# FOUR-INPORT.net
KiCad netlist of a schematic drawn in Altium Designer
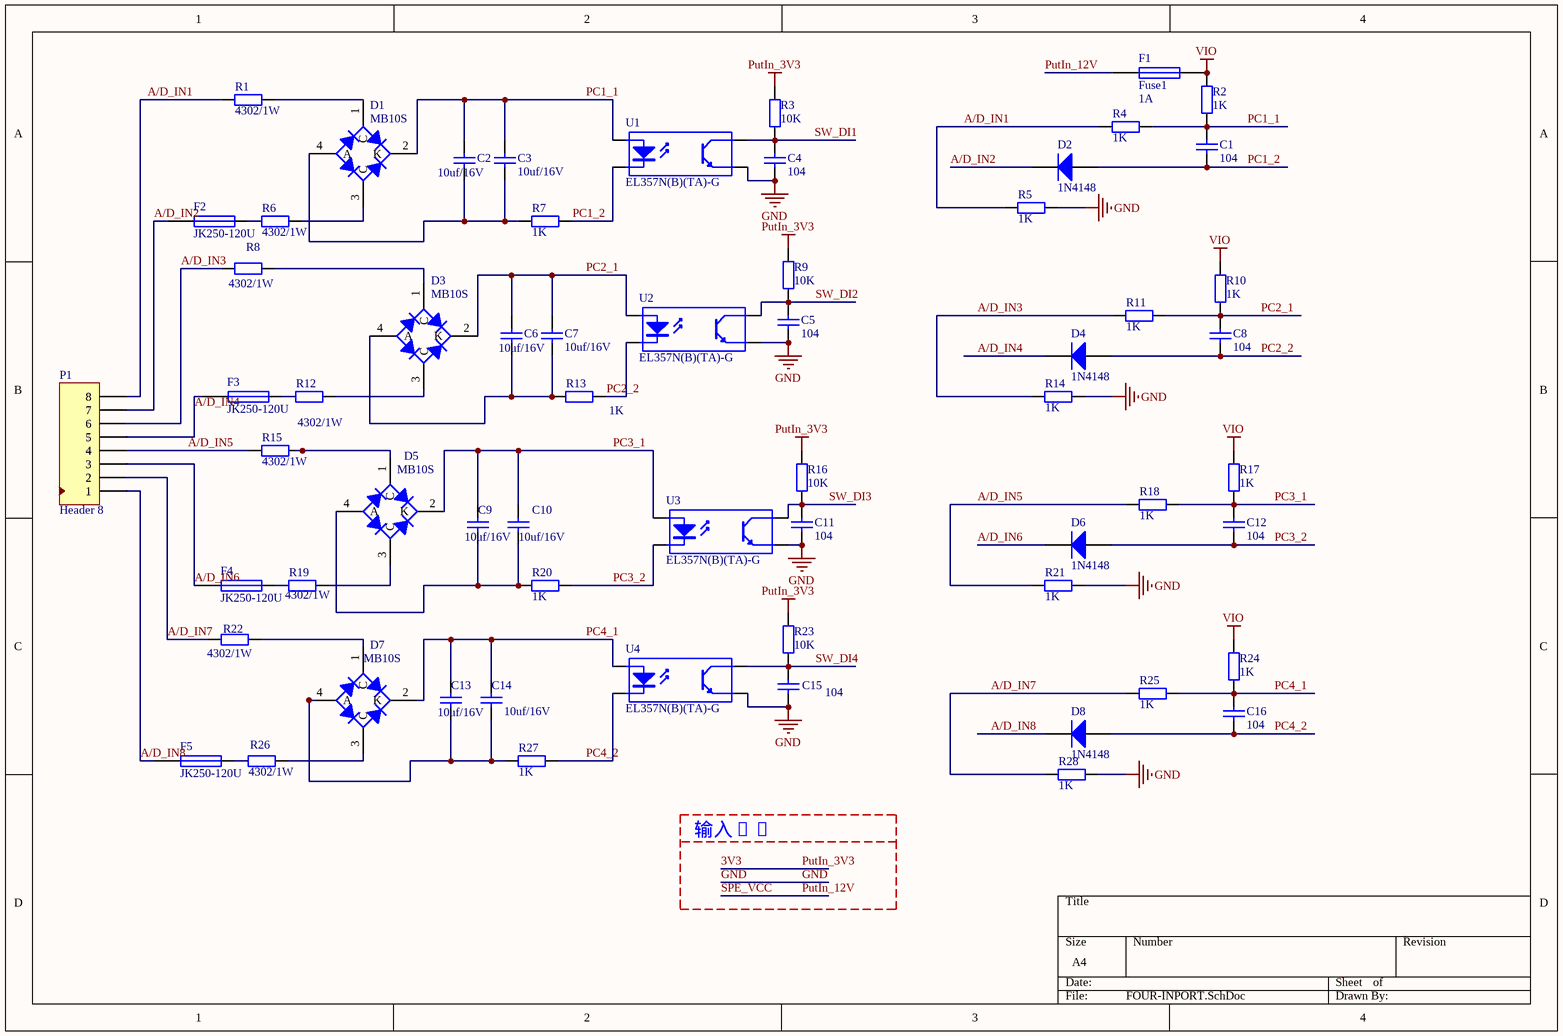
[diagram p0: FOUR-INPORT.SchDoc]

(export (version "E")
  (design (tool "Eeschema 10.0.6"))
  (components
    (comp (ref "C1")
      (value "104")
      (footprint "LC-1206_C")
      (description "Capacitor")
      (fields (field (name "PUBLISHER") "Altium Limited"))
      (libsource (lib "Miscellaneous Devices") (part "Cap"))
    )
    (comp (ref "C2")
      (value "10uf/16V")
      (footprint "LC-0805_C")
      (description "Capacitor")
      (fields (field (name "PUBLISHER") "Altium Limited"))
      (libsource (lib "Miscellaneous Devices") (part "Cap"))
    )
    (comp (ref "C3")
      (value "10uf/16V")
      (footprint "LC-0805_C")
      (description "Capacitor")
      (fields (field (name "PUBLISHER") "Altium Limited"))
      (libsource (lib "Miscellaneous Devices") (part "Cap"))
    )
    (comp (ref "C4")
      (value "104")
      (footprint "LC-0603_C")
      (description "Capacitor")
      (fields (field (name "PUBLISHER") "Altium Limited"))
      (libsource (lib "Miscellaneous Devices") (part "Cap"))
    )
    (comp (ref "C5")
      (value "104")
      (footprint "LC-0603_C")
      (description "Capacitor")
      (fields (field (name "PUBLISHER") "Altium Limited"))
      (libsource (lib "Miscellaneous Devices") (part "Cap"))
    )
    (comp (ref "C6")
      (value "10uf/16V")
      (footprint "LC-0805_C")
      (description "Capacitor")
      (fields (field (name "PUBLISHER") "Altium Limited"))
      (libsource (lib "Miscellaneous Devices") (part "Cap"))
    )
    (comp (ref "C7")
      (value "10uf/16V")
      (footprint "LC-0805_C")
      (description "Capacitor")
      (fields (field (name "PUBLISHER") "Altium Limited"))
      (libsource (lib "Miscellaneous Devices") (part "Cap"))
    )
    (comp (ref "C8")
      (value "104")
      (footprint "LC-1206_C")
      (description "Capacitor")
      (fields (field (name "PUBLISHER") "Altium Limited"))
      (libsource (lib "Miscellaneous Devices") (part "Cap"))
    )
    (comp (ref "C9")
      (value "10uf/16V")
      (footprint "LC-0805_C")
      (description "Capacitor")
      (fields (field (name "PUBLISHER") "Altium Limited"))
      (libsource (lib "Miscellaneous Devices") (part "Cap"))
    )
    (comp (ref "C10")
      (value "10uf/16V")
      (footprint "LC-0805_C")
      (description "Capacitor")
      (fields (field (name "PUBLISHER") "Altium Limited"))
      (libsource (lib "Miscellaneous Devices") (part "Cap"))
    )
    (comp (ref "C11")
      (value "104")
      (footprint "LC-0603_C")
      (description "Capacitor")
      (fields (field (name "PUBLISHER") "Altium Limited"))
      (libsource (lib "Miscellaneous Devices") (part "Cap"))
    )
    (comp (ref "C12")
      (value "104")
      (footprint "LC-1206_C")
      (description "Capacitor")
      (fields (field (name "PUBLISHER") "Altium Limited"))
      (libsource (lib "Miscellaneous Devices") (part "Cap"))
    )
    (comp (ref "C13")
      (value "10uf/16V")
      (footprint "LC-0805_C")
      (description "Capacitor")
      (fields (field (name "PUBLISHER") "Altium Limited"))
      (libsource (lib "Miscellaneous Devices") (part "Cap"))
    )
    (comp (ref "C14")
      (value "10uf/16V")
      (footprint "LC-0805_C")
      (description "Capacitor")
      (fields (field (name "PUBLISHER") "Altium Limited"))
      (libsource (lib "Miscellaneous Devices") (part "Cap"))
    )
    (comp (ref "C15")
      (value "104")
      (footprint "LC-0603_C")
      (description "Capacitor")
      (fields (field (name "PUBLISHER") "Altium Limited"))
      (libsource (lib "Miscellaneous Devices") (part "Cap"))
    )
    (comp (ref "C16")
      (value "104")
      (footprint "LC-1206_C")
      (description "Capacitor")
      (fields (field (name "PUBLISHER") "Altium Limited"))
      (libsource (lib "Miscellaneous Devices") (part "Cap"))
    )
    (comp (ref "D1")
      (value "MB10S")
      (footprint "LC-MBS")
      (description "整流桥")
      (libsource (lib "Miscellaneous Devices LC") (part "MBS MB10S"))
    )
    (comp (ref "D2")
      (value "1N4148")
      (footprint "LC-LL-34")
      (description "Default Diode")
      (fields (field (name "PUBLISHER") "Altium Limited"))
      (libsource (lib "Miscellaneous Devices") (part "Diode"))
    )
    (comp (ref "D3")
      (value "MB10S")
      (footprint "LC-MBS")
      (description "整流桥")
      (libsource (lib "Miscellaneous Devices LC") (part "MBS MB10S"))
    )
    (comp (ref "D4")
      (value "1N4148")
      (footprint "LC-LL-34")
      (description "Default Diode")
      (fields (field (name "PUBLISHER") "Altium Limited"))
      (libsource (lib "Miscellaneous Devices") (part "Diode"))
    )
    (comp (ref "D5")
      (value "MB10S")
      (footprint "LC-MBS")
      (description "整流桥")
      (libsource (lib "Miscellaneous Devices LC") (part "MBS MB10S"))
    )
    (comp (ref "D6")
      (value "1N4148")
      (footprint "LC-LL-34")
      (description "Default Diode")
      (fields (field (name "PUBLISHER") "Altium Limited"))
      (libsource (lib "Miscellaneous Devices") (part "Diode"))
    )
    (comp (ref "D7")
      (value "MB10S")
      (footprint "LC-MBS")
      (description "整流桥")
      (libsource (lib "Miscellaneous Devices LC") (part "MBS MB10S"))
    )
    (comp (ref "D8")
      (value "1N4148")
      (footprint "LC-LL-34")
      (description "Default Diode")
      (fields (field (name "PUBLISHER") "Altium Limited"))
      (libsource (lib "Miscellaneous Devices") (part "Diode"))
    )
    (comp (ref "F1")
      (value "Fuse1")
      (footprint "LC-1206_R")
      (description "保险丝")
      (fields (field (name "ALTIUM_VALUE") "1A"))
      (libsource (lib "fszhang") (part "Fuse1"))
    )
    (comp (ref "F2")
      (value "JK250-120U")
      (footprint "ntc250v")
      (description "保险丝")
      (libsource (lib "SCH_Footp1_Lian") (part "Fuse1"))
    )
    (comp (ref "F3")
      (value "JK250-120U")
      (footprint "ntc250v")
      (description "保险丝")
      (libsource (lib "SCH_Footp1_Lian") (part "Fuse1"))
    )
    (comp (ref "F4")
      (value "JK250-120U")
      (footprint "ntc250v")
      (description "保险丝")
      (libsource (lib "SCH_Footp1_Lian") (part "Fuse1"))
    )
    (comp (ref "F5")
      (value "JK250-120U")
      (footprint "ntc250v")
      (description "保险丝")
      (libsource (lib "SCH_Footp1_Lian") (part "Fuse1"))
    )
    (comp (ref "P1")
      (value "Header 8")
      (footprint "5.08-8p")
      (description "接插件")
      (fields (field (name "PUBLISHER") "Altium Limited"))
      (libsource (lib "HDR_fszhang") (part "Header 8"))
    )
    (comp (ref "R1")
      (value "4302/1W")
      (footprint "LC-2512_R")
      (description "Resistor")
      (fields (field (name "PUBLISHER") "Altium Limited"))
      (libsource (lib "Miscellaneous Devices") (part "Res2"))
    )
    (comp (ref "R2")
      (value "1K")
      (footprint "LC-1206_R")
      (description "贴片电阻")
      (fields (field (name "Comment") "Res1") (field (name "PUBLISHER") "Altium Limited"))
      (libsource (lib "") (part "Res1_1"))
    )
    (comp (ref "R3")
      (value "10K")
      (footprint "LC-0603_R")
      (description "Resistor")
      (fields (field (name "PUBLISHER") "Altium Limited"))
      (libsource (lib "") (part "Res2_1"))
    )
    (comp (ref "R4")
      (value "1K")
      (footprint "LC-1206_R")
      (description "贴片电阻")
      (fields (field (name "Comment") "Res1") (field (name "PUBLISHER") "Altium Limited"))
      (libsource (lib "fszhang") (part "Res1"))
    )
    (comp (ref "R5")
      (value "1K")
      (footprint "LC-1206_R")
      (description "贴片电阻")
      (fields (field (name "Comment") "Res1") (field (name "PUBLISHER") "Altium Limited"))
      (libsource (lib "fszhang") (part "Res1"))
    )
    (comp (ref "R6")
      (value "4302/1W")
      (footprint "LC-2512_R")
      (description "Resistor")
      (fields (field (name "PUBLISHER") "Altium Limited"))
      (libsource (lib "Miscellaneous Devices") (part "Res2"))
    )
    (comp (ref "R7")
      (value "1K")
      (footprint "LC-0603_R")
      (description "Resistor")
      (fields (field (name "PUBLISHER") "Altium Limited"))
      (libsource (lib "") (part "Res2_2"))
    )
    (comp (ref "R8")
      (value "4302/1W")
      (footprint "LC-2512_R")
      (description "Resistor")
      (fields (field (name "PUBLISHER") "Altium Limited"))
      (libsource (lib "Miscellaneous Devices") (part "Res2"))
    )
    (comp (ref "R9")
      (value "10K")
      (footprint "LC-0603_R")
      (description "Resistor")
      (fields (field (name "PUBLISHER") "Altium Limited"))
      (libsource (lib "") (part "Res2_1"))
    )
    (comp (ref "R10")
      (value "1K")
      (footprint "LC-1206_R")
      (description "贴片电阻")
      (fields (field (name "Comment") "Res1") (field (name "PUBLISHER") "Altium Limited"))
      (libsource (lib "") (part "Res1_2"))
    )
    (comp (ref "R11")
      (value "1K")
      (footprint "LC-1206_R")
      (description "贴片电阻")
      (fields (field (name "Comment") "Res1") (field (name "PUBLISHER") "Altium Limited"))
      (libsource (lib "fszhang") (part "Res1"))
    )
    (comp (ref "R12")
      (value "4302/1W")
      (footprint "LC-2512_R")
      (description "Resistor")
      (fields (field (name "PUBLISHER") "Altium Limited"))
      (libsource (lib "Miscellaneous Devices") (part "Res2"))
    )
    (comp (ref "R13")
      (value "1K")
      (footprint "LC-0603_R")
      (description "Resistor")
      (fields (field (name "PUBLISHER") "Altium Limited"))
      (libsource (lib "") (part "Res2_2"))
    )
    (comp (ref "R14")
      (value "1K")
      (footprint "LC-1206_R")
      (description "贴片电阻")
      (fields (field (name "Comment") "Res1") (field (name "PUBLISHER") "Altium Limited"))
      (libsource (lib "fszhang") (part "Res1"))
    )
    (comp (ref "R15")
      (value "4302/1W")
      (footprint "LC-2512_R")
      (description "Resistor")
      (fields (field (name "PUBLISHER") "Altium Limited"))
      (libsource (lib "Miscellaneous Devices") (part "Res2"))
    )
    (comp (ref "R16")
      (value "10K")
      (footprint "LC-0603_R")
      (description "Resistor")
      (fields (field (name "PUBLISHER") "Altium Limited"))
      (libsource (lib "") (part "Res2_1"))
    )
    (comp (ref "R17")
      (value "1K")
      (footprint "LC-1206_R")
      (description "贴片电阻")
      (fields (field (name "Comment") "Res1") (field (name "PUBLISHER") "Altium Limited"))
      (libsource (lib "") (part "Res1_2"))
    )
    (comp (ref "R18")
      (value "1K")
      (footprint "LC-1206_R")
      (description "贴片电阻")
      (fields (field (name "Comment") "Res1") (field (name "PUBLISHER") "Altium Limited"))
      (libsource (lib "fszhang") (part "Res1"))
    )
    (comp (ref "R19")
      (value "4302/1W")
      (footprint "LC-2512_R")
      (description "Resistor")
      (fields (field (name "PUBLISHER") "Altium Limited"))
      (libsource (lib "Miscellaneous Devices") (part "Res2"))
    )
    (comp (ref "R20")
      (value "1K")
      (footprint "LC-0603_R")
      (description "Resistor")
      (fields (field (name "PUBLISHER") "Altium Limited"))
      (libsource (lib "") (part "Res2_2"))
    )
    (comp (ref "R21")
      (value "1K")
      (footprint "LC-1206_R")
      (description "贴片电阻")
      (fields (field (name "Comment") "Res1") (field (name "PUBLISHER") "Altium Limited"))
      (libsource (lib "fszhang") (part "Res1"))
    )
    (comp (ref "R22")
      (value "4302/1W")
      (footprint "LC-2512_R")
      (description "Resistor")
      (fields (field (name "PUBLISHER") "Altium Limited"))
      (libsource (lib "Miscellaneous Devices") (part "Res2"))
    )
    (comp (ref "R23")
      (value "10K")
      (footprint "LC-0603_R")
      (description "Resistor")
      (fields (field (name "PUBLISHER") "Altium Limited"))
      (libsource (lib "") (part "Res2_1"))
    )
    (comp (ref "R24")
      (value "1K")
      (footprint "LC-1206_R")
      (description "贴片电阻")
      (fields (field (name "Comment") "Res1") (field (name "PUBLISHER") "Altium Limited"))
      (libsource (lib "") (part "Res1_2"))
    )
    (comp (ref "R25")
      (value "1K")
      (footprint "LC-1206_R")
      (description "贴片电阻")
      (fields (field (name "Comment") "Res1") (field (name "PUBLISHER") "Altium Limited"))
      (libsource (lib "fszhang") (part "Res1"))
    )
    (comp (ref "R26")
      (value "4302/1W")
      (footprint "LC-2512_R")
      (description "Resistor")
      (fields (field (name "PUBLISHER") "Altium Limited"))
      (libsource (lib "Miscellaneous Devices") (part "Res2"))
    )
    (comp (ref "R27")
      (value "1K")
      (footprint "LC-0603_R")
      (description "Resistor")
      (fields (field (name "PUBLISHER") "Altium Limited"))
      (libsource (lib "") (part "Res2_2"))
    )
    (comp (ref "R28")
      (value "1K")
      (footprint "LC-1206_R")
      (description "贴片电阻")
      (fields (field (name "Comment") "Res1") (field (name "PUBLISHER") "Altium Limited"))
      (libsource (lib "fszhang") (part "Res1"))
    )
    (comp (ref "U1")
      (value "EL357N(B)(TA)-G")
      (footprint "LC-SOP-4_P2.54")
      (description "贴片光耦")
      (libsource (lib "Miscellaneous Devices LC") (part "EL357N(B)(TA)-G"))
    )
    (comp (ref "U2")
      (value "EL357N(B)(TA)-G")
      (footprint "LC-SOP-4_P2.54")
      (description "贴片光耦")
      (libsource (lib "Miscellaneous Devices LC") (part "EL357N(B)(TA)-G"))
    )
    (comp (ref "U3")
      (value "EL357N(B)(TA)-G")
      (footprint "LC-SOP-4_P2.54")
      (description "贴片光耦")
      (libsource (lib "Miscellaneous Devices LC") (part "EL357N(B)(TA)-G"))
    )
    (comp (ref "U4")
      (value "EL357N(B)(TA)-G")
      (footprint "LC-SOP-4_P2.54")
      (description "贴片光耦")
      (libsource (lib "Miscellaneous Devices LC") (part "EL357N(B)(TA)-G"))
    )
  )
  (nets
    (net (code "1") (name "/A{slash}D_IN1") (class "Default")
      (node (ref "P1") (pin "8") (pinfunction "8_8") (pintype "passive"))
      (node (ref "R1") (pin "1") (pinfunction "1_1") (pintype "passive"))
      (node (ref "R4") (pin "2") (pinfunction "2_2") (pintype "passive"))
      (node (ref "R5") (pin "2") (pinfunction "2_2") (pintype "passive"))
    )
    (net (code "2") (name "/A{slash}D_IN2") (class "Default")
      (node (ref "D2") (pin "2") (pinfunction "K_2") (pintype "passive"))
      (node (ref "F2") (pin "1") (pinfunction "1_1") (pintype "passive"))
      (node (ref "P1") (pin "7") (pinfunction "7_7") (pintype "passive"))
    )
    (net (code "3") (name "/A{slash}D_IN3") (class "Default")
      (node (ref "P1") (pin "6") (pinfunction "6_6") (pintype "passive"))
      (node (ref "R11") (pin "2") (pinfunction "2_2") (pintype "passive"))
      (node (ref "R14") (pin "2") (pinfunction "2_2") (pintype "passive"))
      (node (ref "R8") (pin "1") (pinfunction "1_1") (pintype "passive"))
    )
    (net (code "4") (name "/A{slash}D_IN4") (class "Default")
      (node (ref "D4") (pin "2") (pinfunction "K_2") (pintype "passive"))
      (node (ref "F3") (pin "1") (pinfunction "1_1") (pintype "passive"))
      (node (ref "P1") (pin "5") (pinfunction "5_5") (pintype "passive"))
    )
    (net (code "5") (name "/A{slash}D_IN5") (class "Default")
      (node (ref "P1") (pin "4") (pinfunction "4_4") (pintype "passive"))
      (node (ref "R15") (pin "1") (pinfunction "1_1") (pintype "passive"))
      (node (ref "R18") (pin "2") (pinfunction "2_2") (pintype "passive"))
      (node (ref "R21") (pin "2") (pinfunction "2_2") (pintype "passive"))
    )
    (net (code "6") (name "/A{slash}D_IN6") (class "Default")
      (node (ref "D6") (pin "2") (pinfunction "K_2") (pintype "passive"))
      (node (ref "F4") (pin "1") (pinfunction "1_1") (pintype "passive"))
      (node (ref "P1") (pin "3") (pinfunction "3_3") (pintype "passive"))
    )
    (net (code "7") (name "/A{slash}D_IN7") (class "Default")
      (node (ref "P1") (pin "2") (pinfunction "2_2") (pintype "passive"))
      (node (ref "R22") (pin "1") (pinfunction "1_1") (pintype "passive"))
      (node (ref "R25") (pin "2") (pinfunction "2_2") (pintype "passive"))
      (node (ref "R28") (pin "2") (pinfunction "2_2") (pintype "passive"))
    )
    (net (code "8") (name "/A{slash}D_IN8") (class "Default")
      (node (ref "D8") (pin "2") (pinfunction "K_2") (pintype "passive"))
      (node (ref "F5") (pin "1") (pinfunction "1_1") (pintype "passive"))
      (node (ref "P1") (pin "1") (pinfunction "1_1") (pintype "passive"))
    )
    (net (code "9") (name "/PC1_1") (class "Default")
      (node (ref "C1") (pin "1") (pinfunction "1_1") (pintype "passive"))
      (node (ref "C2") (pin "2") (pinfunction "2_2") (pintype "passive"))
      (node (ref "C3") (pin "2") (pinfunction "2_2") (pintype "passive"))
      (node (ref "D1") (pin "2") (pinfunction "K_2") (pintype "passive"))
      (node (ref "R2") (pin "1") (pinfunction "1_1") (pintype "passive"))
      (node (ref "R4") (pin "1") (pinfunction "1_1") (pintype "passive"))
      (node (ref "U1") (pin "1") (pinfunction "A_1") (pintype "passive"))
    )
    (net (code "10") (name "/PC1_2") (class "Default")
      (node (ref "C1") (pin "2") (pinfunction "2_2") (pintype "passive"))
      (node (ref "D2") (pin "1") (pinfunction "A_1") (pintype "passive"))
      (node (ref "R7") (pin "1") (pinfunction "1_1") (pintype "passive"))
      (node (ref "U1") (pin "2") (pinfunction "K_2") (pintype "passive"))
    )
    (net (code "11") (name "/PC2_1") (class "Default")
      (node (ref "C6") (pin "2") (pinfunction "2_2") (pintype "passive"))
      (node (ref "C7") (pin "2") (pinfunction "2_2") (pintype "passive"))
      (node (ref "C8") (pin "1") (pinfunction "1_1") (pintype "passive"))
      (node (ref "D3") (pin "2") (pinfunction "K_2") (pintype "passive"))
      (node (ref "R10") (pin "2") (pinfunction "2_2") (pintype "passive"))
      (node (ref "R11") (pin "1") (pinfunction "1_1") (pintype "passive"))
      (node (ref "U2") (pin "1") (pinfunction "A_1") (pintype "passive"))
    )
    (net (code "12") (name "/PC2_2") (class "Default")
      (node (ref "C8") (pin "2") (pinfunction "2_2") (pintype "passive"))
      (node (ref "D4") (pin "1") (pinfunction "A_1") (pintype "passive"))
      (node (ref "R13") (pin "1") (pinfunction "1_1") (pintype "passive"))
      (node (ref "U2") (pin "2") (pinfunction "K_2") (pintype "passive"))
    )
    (net (code "13") (name "/PC3_1") (class "Default")
      (node (ref "C10") (pin "2") (pinfunction "2_2") (pintype "passive"))
      (node (ref "C12") (pin "1") (pinfunction "1_1") (pintype "passive"))
      (node (ref "C9") (pin "2") (pinfunction "2_2") (pintype "passive"))
      (node (ref "D5") (pin "2") (pinfunction "K_2") (pintype "passive"))
      (node (ref "R17") (pin "2") (pinfunction "2_2") (pintype "passive"))
      (node (ref "R18") (pin "1") (pinfunction "1_1") (pintype "passive"))
      (node (ref "U3") (pin "1") (pinfunction "A_1") (pintype "passive"))
    )
    (net (code "14") (name "/PC3_2") (class "Default")
      (node (ref "C12") (pin "2") (pinfunction "2_2") (pintype "passive"))
      (node (ref "D6") (pin "1") (pinfunction "A_1") (pintype "passive"))
      (node (ref "R20") (pin "1") (pinfunction "1_1") (pintype "passive"))
      (node (ref "U3") (pin "2") (pinfunction "K_2") (pintype "passive"))
    )
    (net (code "15") (name "/PC4_1") (class "Default")
      (node (ref "C13") (pin "2") (pinfunction "2_2") (pintype "passive"))
      (node (ref "C14") (pin "2") (pinfunction "2_2") (pintype "passive"))
      (node (ref "C16") (pin "1") (pinfunction "1_1") (pintype "passive"))
      (node (ref "D7") (pin "2") (pinfunction "K_2") (pintype "passive"))
      (node (ref "R24") (pin "2") (pinfunction "2_2") (pintype "passive"))
      (node (ref "R25") (pin "1") (pinfunction "1_1") (pintype "passive"))
      (node (ref "U4") (pin "1") (pinfunction "A_1") (pintype "passive"))
    )
    (net (code "16") (name "/PC4_2") (class "Default")
      (node (ref "C16") (pin "2") (pinfunction "2_2") (pintype "passive"))
      (node (ref "D8") (pin "1") (pinfunction "A_1") (pintype "passive"))
      (node (ref "R27") (pin "1") (pinfunction "1_1") (pintype "passive"))
      (node (ref "U4") (pin "2") (pinfunction "K_2") (pintype "passive"))
    )
    (net (code "17") (name "/PutIn_12V") (class "Default")
      (node (ref "F1") (pin "1") (pinfunction "1_1") (pintype "passive"))
    )
    (net (code "18") (name "/SW_DI1") (class "Default")
      (node (ref "C4") (pin "1") (pinfunction "1_1") (pintype "passive"))
      (node (ref "R3") (pin "1") (pinfunction "1_1") (pintype "passive"))
      (node (ref "U1") (pin "4") (pinfunction "C_4") (pintype "passive"))
    )
    (net (code "19") (name "/SW_DI2") (class "Default")
      (node (ref "C5") (pin "1") (pinfunction "1_1") (pintype "passive"))
      (node (ref "R9") (pin "1") (pinfunction "1_1") (pintype "passive"))
      (node (ref "U2") (pin "4") (pinfunction "C_4") (pintype "passive"))
    )
    (net (code "20") (name "/SW_DI3") (class "Default")
      (node (ref "C11") (pin "1") (pinfunction "1_1") (pintype "passive"))
      (node (ref "R16") (pin "1") (pinfunction "1_1") (pintype "passive"))
      (node (ref "U3") (pin "4") (pinfunction "C_4") (pintype "passive"))
    )
    (net (code "21") (name "/SW_DI4") (class "Default")
      (node (ref "C15") (pin "1") (pinfunction "1_1") (pintype "passive"))
      (node (ref "R23") (pin "1") (pinfunction "1_1") (pintype "passive"))
      (node (ref "U4") (pin "4") (pinfunction "C_4") (pintype "passive"))
    )
    (net (code "22") (name "GND") (class "Default")
      (node (ref "C11") (pin "2") (pinfunction "2_2") (pintype "passive"))
      (node (ref "C15") (pin "2") (pinfunction "2_2") (pintype "passive"))
      (node (ref "C4") (pin "2") (pinfunction "2_2") (pintype "passive"))
      (node (ref "C5") (pin "2") (pinfunction "2_2") (pintype "passive"))
      (node (ref "R14") (pin "1") (pinfunction "1_1") (pintype "passive"))
      (node (ref "R21") (pin "1") (pinfunction "1_1") (pintype "passive"))
      (node (ref "R28") (pin "1") (pinfunction "1_1") (pintype "passive"))
      (node (ref "R5") (pin "1") (pinfunction "1_1") (pintype "passive"))
      (node (ref "U1") (pin "3") (pinfunction "E_3") (pintype "passive"))
      (node (ref "U2") (pin "3") (pinfunction "E_3") (pintype "passive"))
      (node (ref "U3") (pin "3") (pinfunction "E_3") (pintype "passive"))
      (node (ref "U4") (pin "3") (pinfunction "E_3") (pintype "passive"))
    )
    (net (code "23") (name "Net-(D1-A)") (class "Default")
      (node (ref "C2") (pin "1") (pinfunction "1_1") (pintype "passive"))
      (node (ref "C3") (pin "1") (pinfunction "1_1") (pintype "passive"))
      (node (ref "D1") (pin "4") (pinfunction "A_4") (pintype "passive"))
      (node (ref "R7") (pin "2") (pinfunction "2_2") (pintype "passive"))
    )
    (net (code "24") (name "Net-(D1-C-Pad1)") (class "Default")
      (node (ref "D1") (pin "1") (pinfunction "C_1") (pintype "passive"))
      (node (ref "R1") (pin "2") (pinfunction "2_2") (pintype "passive"))
    )
    (net (code "25") (name "Net-(D1-C-Pad3)") (class "Default")
      (node (ref "D1") (pin "3") (pinfunction "C_3") (pintype "passive"))
      (node (ref "R6") (pin "2") (pinfunction "2_2") (pintype "passive"))
    )
    (net (code "26") (name "Net-(D3-A)") (class "Default")
      (node (ref "C6") (pin "1") (pinfunction "1_1") (pintype "passive"))
      (node (ref "C7") (pin "1") (pinfunction "1_1") (pintype "passive"))
      (node (ref "D3") (pin "4") (pinfunction "A_4") (pintype "passive"))
      (node (ref "R13") (pin "2") (pinfunction "2_2") (pintype "passive"))
    )
    (net (code "27") (name "Net-(D3-C-Pad1)") (class "Default")
      (node (ref "D3") (pin "1") (pinfunction "C_1") (pintype "passive"))
      (node (ref "R8") (pin "2") (pinfunction "2_2") (pintype "passive"))
    )
    (net (code "28") (name "Net-(D3-C-Pad3)") (class "Default")
      (node (ref "D3") (pin "3") (pinfunction "C_3") (pintype "passive"))
      (node (ref "R12") (pin "2") (pinfunction "2_2") (pintype "passive"))
    )
    (net (code "29") (name "Net-(D5-A)") (class "Default")
      (node (ref "C10") (pin "1") (pinfunction "1_1") (pintype "passive"))
      (node (ref "C9") (pin "1") (pinfunction "1_1") (pintype "passive"))
      (node (ref "D5") (pin "4") (pinfunction "A_4") (pintype "passive"))
      (node (ref "R20") (pin "2") (pinfunction "2_2") (pintype "passive"))
    )
    (net (code "30") (name "Net-(D5-C-Pad1)") (class "Default")
      (node (ref "D5") (pin "1") (pinfunction "C_1") (pintype "passive"))
      (node (ref "R15") (pin "2") (pinfunction "2_2") (pintype "passive"))
    )
    (net (code "31") (name "Net-(D5-C-Pad3)") (class "Default")
      (node (ref "D5") (pin "3") (pinfunction "C_3") (pintype "passive"))
      (node (ref "R19") (pin "2") (pinfunction "2_2") (pintype "passive"))
    )
    (net (code "32") (name "Net-(D7-A)") (class "Default")
      (node (ref "C13") (pin "1") (pinfunction "1_1") (pintype "passive"))
      (node (ref "C14") (pin "1") (pinfunction "1_1") (pintype "passive"))
      (node (ref "D7") (pin "4") (pinfunction "A_4") (pintype "passive"))
      (node (ref "R27") (pin "2") (pinfunction "2_2") (pintype "passive"))
    )
    (net (code "33") (name "Net-(D7-C-Pad1)") (class "Default")
      (node (ref "D7") (pin "1") (pinfunction "C_1") (pintype "passive"))
      (node (ref "R22") (pin "2") (pinfunction "2_2") (pintype "passive"))
    )
    (net (code "34") (name "Net-(D7-C-Pad3)") (class "Default")
      (node (ref "D7") (pin "3") (pinfunction "C_3") (pintype "passive"))
      (node (ref "R26") (pin "2") (pinfunction "2_2") (pintype "passive"))
    )
    (net (code "35") (name "Net-(F2-Pad2)") (class "Default")
      (node (ref "F2") (pin "2") (pinfunction "2_2") (pintype "passive"))
      (node (ref "R6") (pin "1") (pinfunction "1_1") (pintype "passive"))
    )
    (net (code "36") (name "Net-(F3-Pad2)") (class "Default")
      (node (ref "F3") (pin "2") (pinfunction "2_2") (pintype "passive"))
      (node (ref "R12") (pin "1") (pinfunction "1_1") (pintype "passive"))
    )
    (net (code "37") (name "Net-(F4-Pad2)") (class "Default")
      (node (ref "F4") (pin "2") (pinfunction "2_2") (pintype "passive"))
      (node (ref "R19") (pin "1") (pinfunction "1_1") (pintype "passive"))
    )
    (net (code "38") (name "Net-(F5-Pad2)") (class "Default")
      (node (ref "F5") (pin "2") (pinfunction "2_2") (pintype "passive"))
      (node (ref "R26") (pin "1") (pinfunction "1_1") (pintype "passive"))
    )
    (net (code "39") (name "PutIn_3V3") (class "Default")
      (node (ref "R16") (pin "2") (pinfunction "2_2") (pintype "passive"))
      (node (ref "R23") (pin "2") (pinfunction "2_2") (pintype "passive"))
      (node (ref "R3") (pin "2") (pinfunction "2_2") (pintype "passive"))
      (node (ref "R9") (pin "2") (pinfunction "2_2") (pintype "passive"))
    )
    (net (code "40") (name "VIO") (class "Default")
      (node (ref "F1") (pin "2") (pinfunction "2_2") (pintype "passive"))
      (node (ref "R10") (pin "1") (pinfunction "1_1") (pintype "passive"))
      (node (ref "R17") (pin "1") (pinfunction "1_1") (pintype "passive"))
      (node (ref "R2") (pin "2") (pinfunction "2_2") (pintype "passive"))
      (node (ref "R24") (pin "1") (pinfunction "1_1") (pintype "passive"))
    )
  )
)
